# schemat.net
KiCad netlist of a schematic drawn in EAGLE
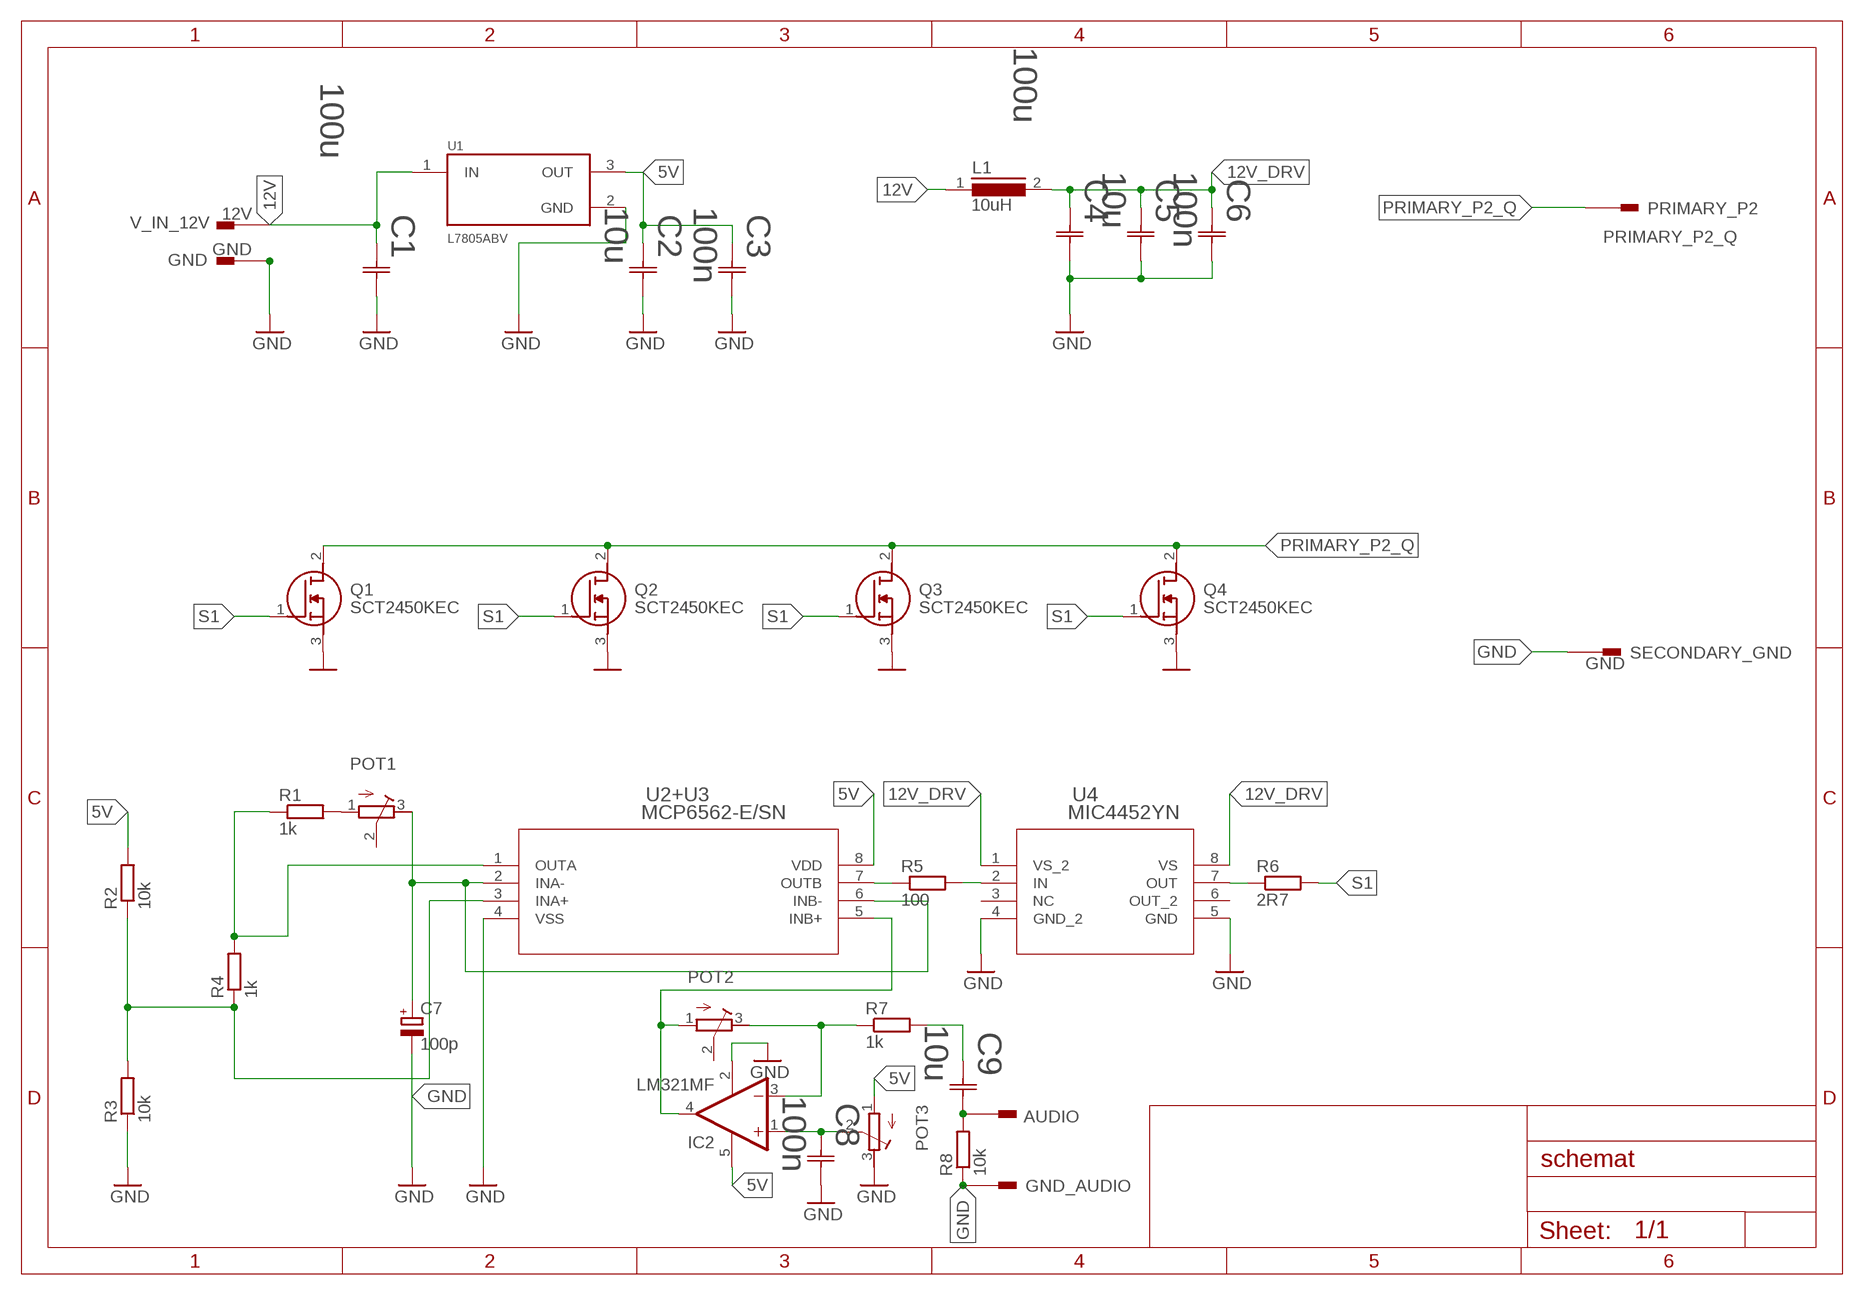
[diagram p0: schematic, sheet 1]

(export (version "E")
  (design (tool "Eeschema 10.0.6"))
  (components
    (comp (ref "AUDIO")
      (value "PIN1-2")
      (footprint "eagle-import:62221")
      (fields (field (name "MF") "TYCO ELECTRONICS") (field (name "MPN") "62221-1"))
      (libsource (lib "eagle-import") (part "PIN1-2"))
    )
    (comp (ref "C1")
      (value "100u")
      (footprint "eagle-import:CAP_YX_6P3X11_RUB")
      (fields
        (field (name "MANUFACTURER_PART_NUMBER") "35ZLH100MEFC6.3X11")
        (field (name "COPYRIGHT") "Copyright (C) 2024 Ultra Librarian. All rights reserved.")
      )
      (libsource (lib "eagle-import") (part "35ZLH100MEFC6.3X11"))
    )
    (comp (ref "C2")
      (value "10u")
      (footprint "eagle-import:CAP_5_X_5_PAN")
      (fields
        (field (name "MANUFACTURER_PART_NUMBER") "ECEA1EKS100")
        (field (name "COPYRIGHT") "Copyright (C) 2024 Ultra Librarian. All rights reserved.")
      )
      (libsource (lib "eagle-import") (part "ECEA1EKS100"))
    )
    (comp (ref "C3")
      (value "100n")
      (footprint "eagle-import:CAP_0402_WAL")
      (fields
        (field (name "MANUFACTURER_PART_NUMBER") "0402B104K250CT")
        (field (name "COPYRIGHT") "Copyright (C) 2024 Ultra Librarian. All rights reserved.")
      )
      (libsource (lib "eagle-import") (part "0402B104K250CT"))
    )
    (comp (ref "C4")
      (value "100u")
      (footprint "eagle-import:CAP_YX_6P3X11_RUB")
      (fields
        (field (name "MANUFACTURER_PART_NUMBER") "35ZLH100MEFC6.3X11")
        (field (name "COPYRIGHT") "Copyright (C) 2024 Ultra Librarian. All rights reserved.")
      )
      (libsource (lib "eagle-import") (part "35ZLH100MEFC6.3X11"))
    )
    (comp (ref "C5")
      (value "10u")
      (footprint "eagle-import:CAP_5_X_5_PAN")
      (fields
        (field (name "MANUFACTURER_PART_NUMBER") "ECEA1EKS100")
        (field (name "COPYRIGHT") "Copyright (C) 2024 Ultra Librarian. All rights reserved.")
      )
      (libsource (lib "eagle-import") (part "ECEA1EKS100"))
    )
    (comp (ref "C6")
      (value "100n")
      (footprint "eagle-import:CAP_0402_WAL")
      (fields
        (field (name "MANUFACTURER_PART_NUMBER") "0402B104K250CT")
        (field (name "COPYRIGHT") "Copyright (C) 2024 Ultra Librarian. All rights reserved.")
      )
      (libsource (lib "eagle-import") (part "0402B104K250CT"))
    )
    (comp (ref "C7")
      (value "100p")
      (footprint "eagle-import:E1,8-4")
      (libsource (lib "eagle-import") (part "CPOL-EUE1.8-4"))
    )
    (comp (ref "C8")
      (value "100n")
      (footprint "eagle-import:CAP_0402_WAL")
      (fields
        (field (name "MANUFACTURER_PART_NUMBER") "0402B104K250CT")
        (field (name "COPYRIGHT") "Copyright (C) 2024 Ultra Librarian. All rights reserved.")
      )
      (libsource (lib "eagle-import") (part "0402B104K250CT"))
    )
    (comp (ref "C9")
      (value "10u")
      (footprint "eagle-import:CAP_5_X_5_PAN")
      (fields
        (field (name "MANUFACTURER_PART_NUMBER") "ECEA1EKS100")
        (field (name "COPYRIGHT") "Copyright (C) 2024 Ultra Librarian. All rights reserved.")
      )
      (libsource (lib "eagle-import") (part "ECEA1EKS100"))
    )
    (comp (ref "GND")
      (value "GND")
      (footprint "eagle-import:62221")
      (fields (field (name "MF") "TYCO ELECTRONICS") (field (name "MPN") "62221-1"))
      (libsource (lib "eagle-import") (part "PIN1-2"))
    )
    (comp (ref "GND_AUDIO")
      (value "GND")
      (footprint "eagle-import:62221")
      (fields (field (name "MF") "TYCO ELECTRONICS") (field (name "MPN") "62221-1"))
      (libsource (lib "eagle-import") (part "PIN1-2"))
    )
    (comp (ref "IC2")
      (value "LM321MF")
      (footprint "eagle-import:SOT23-5")
      (libsource (lib "eagle-import") (part "LM321?MF"))
    )
    (comp (ref "L1")
      (value "10uH")
      (footprint "eagle-import:RKE4")
      (libsource (lib "eagle-import") (part "RKE4"))
    )
    (comp (ref "POT1")
      (value "R-TRIMM64W")
      (footprint "eagle-import:RTRIM64W")
      (libsource (lib "eagle-import") (part "R-TRIMM64W"))
    )
    (comp (ref "POT2")
      (value "R-TRIMM64W")
      (footprint "eagle-import:RTRIM64W")
      (libsource (lib "eagle-import") (part "R-TRIMM64W"))
    )
    (comp (ref "POT3")
      (value "R-TRIMM64W")
      (footprint "eagle-import:RTRIM64W")
      (libsource (lib "eagle-import") (part "R-TRIMM64W"))
    )
    (comp (ref "PRIMARY_P2")
      (value "PRIMARY_P2_Q")
      (footprint "eagle-import:62221")
      (fields (field (name "MF") "TYCO ELECTRONICS") (field (name "MPN") "62221-1"))
      (libsource (lib "eagle-import") (part "PIN1-2"))
    )
    (comp (ref "Q1")
      (value "SCT2450KEC")
      (footprint "eagle-import:TO545P521X1594X2583-3P")
      (libsource (lib "eagle-import") (part "SCT2450KEC"))
    )
    (comp (ref "Q2")
      (value "SCT2450KEC")
      (footprint "eagle-import:TO545P521X1594X2583-3P")
      (libsource (lib "eagle-import") (part "SCT2450KEC"))
    )
    (comp (ref "Q3")
      (value "SCT2450KEC")
      (footprint "eagle-import:TO545P521X1594X2583-3P")
      (libsource (lib "eagle-import") (part "SCT2450KEC"))
    )
    (comp (ref "Q4")
      (value "SCT2450KEC")
      (footprint "eagle-import:TO545P521X1594X2583-3P")
      (libsource (lib "eagle-import") (part "SCT2450KEC"))
    )
    (comp (ref "R1")
      (value "1k")
      (footprint "eagle-import:0204_7")
      (libsource (lib "eagle-import") (part "R-EU_0204/7"))
    )
    (comp (ref "R2")
      (value "10k")
      (footprint "eagle-import:0204_7")
      (libsource (lib "eagle-import") (part "R-EU_0204/7"))
    )
    (comp (ref "R3")
      (value "10k")
      (footprint "eagle-import:0204_7")
      (libsource (lib "eagle-import") (part "R-EU_0204/7"))
    )
    (comp (ref "R4")
      (value "1k")
      (footprint "eagle-import:0204_7")
      (libsource (lib "eagle-import") (part "R-EU_0204/7"))
    )
    (comp (ref "R5")
      (value "100")
      (footprint "eagle-import:0204_7")
      (libsource (lib "eagle-import") (part "R-EU_0204/7"))
    )
    (comp (ref "R6")
      (value "2R7")
      (footprint "eagle-import:0204_7")
      (libsource (lib "eagle-import") (part "R-EU_0204/7"))
    )
    (comp (ref "R7")
      (value "1k")
      (footprint "eagle-import:0204_7")
      (libsource (lib "eagle-import") (part "R-EU_0204/7"))
    )
    (comp (ref "R8")
      (value "10k")
      (footprint "eagle-import:0204_7")
      (libsource (lib "eagle-import") (part "R-EU_0204/7"))
    )
    (comp (ref "SECONDARY_GND")
      (value "GND")
      (footprint "eagle-import:62221")
      (fields (field (name "MF") "TYCO ELECTRONICS") (field (name "MPN") "62221-1"))
      (libsource (lib "eagle-import") (part "PIN1-2"))
    )
    (comp (ref "U1")
      (value "L7805ABV")
      (footprint "eagle-import:TO254P460X1020X1945-3P")
      (fields (field (name "MF") "STMicroelectronics"))
      (libsource (lib "eagle-import") (part "L7805ABV"))
    )
    (comp (ref "U2+U3")
      (value "MCP6562-E/SN")
      (footprint "eagle-import:SOIC8-N_MC_MCH")
      (fields
        (field (name "MANUFACTURER_PART_NUMBER") "mcp6562-e/sn")
        (field (name "COPYRIGHT") "Copyright (C) 2024 Ultra Librarian. All rights reserved.")
      )
      (libsource (lib "eagle-import") (part "MCP6562-E/SN"))
    )
    (comp (ref "U4")
      (value "MIC4452YN")
      (footprint "eagle-import:PDIP8(N)_MCH")
      (fields (field (name "COPYRIGHT") "Copyright (C) 2024 Ultra Librarian. All rights reserved."))
      (libsource (lib "eagle-import") (part "MIC4452YN"))
    )
    (comp (ref "V_IN_12V")
      (value "12V")
      (footprint "eagle-import:62221")
      (fields (field (name "MF") "TYCO ELECTRONICS") (field (name "MPN") "62221-1"))
      (libsource (lib "eagle-import") (part "PIN1-2"))
    )
  )
  (nets
    (net (code "1") (name "5V") (class "Default")
      (node (ref "C2") (pin "1") (pinfunction "1_1") (pintype "passive"))
      (node (ref "C3") (pin "1") (pinfunction "1_1") (pintype "passive"))
      (node (ref "IC2") (pin "5") (pinfunction "V+_5") (pintype "power_in"))
      (node (ref "POT3") (pin "1") (pinfunction "A_1") (pintype "passive"))
      (node (ref "R2") (pin "2") (pinfunction "2_2") (pintype "passive"))
      (node (ref "U1") (pin "3") (pinfunction "OUT_3") (pintype "output"))
      (node (ref "U2+U3") (pin "8") (pinfunction "VDD_8") (pintype "power_in"))
    )
    (net (code "2") (name "12V") (class "Default")
      (node (ref "C1") (pin "1") (pinfunction "1_1") (pintype "passive"))
      (node (ref "L1") (pin "1") (pinfunction "1_1") (pintype "passive"))
      (node (ref "U1") (pin "1") (pinfunction "IN_1") (pintype "input"))
      (node (ref "V_IN_12V") (pin "1") (pinfunction "1_1") (pintype "passive"))
    )
    (net (code "3") (name "12V_DRV") (class "Default")
      (node (ref "C4") (pin "1") (pinfunction "1_1") (pintype "passive"))
      (node (ref "C5") (pin "1") (pinfunction "1_1") (pintype "passive"))
      (node (ref "C6") (pin "1") (pinfunction "1_1") (pintype "passive"))
      (node (ref "L1") (pin "2") (pinfunction "2_2") (pintype "passive"))
      (node (ref "U4") (pin "1") (pinfunction "VS_2_1") (pintype "power_in"))
      (node (ref "U4") (pin "8") (pinfunction "VS_8") (pintype "power_in"))
    )
    (net (code "4") (name "GND") (class "Default")
      (node (ref "C1") (pin "2") (pinfunction "2_2") (pintype "passive"))
      (node (ref "C2") (pin "2") (pinfunction "2_2") (pintype "passive"))
      (node (ref "C3") (pin "2") (pinfunction "2_2") (pintype "passive"))
      (node (ref "C4") (pin "2") (pinfunction "2_2") (pintype "passive"))
      (node (ref "C5") (pin "2") (pinfunction "2_2") (pintype "passive"))
      (node (ref "C6") (pin "2") (pinfunction "2_2") (pintype "passive"))
      (node (ref "C7") (pin "-") (pinfunction "-_-") (pintype "passive"))
      (node (ref "C8") (pin "2") (pinfunction "2_2") (pintype "passive"))
      (node (ref "GND") (pin "1") (pinfunction "1_1") (pintype "passive"))
      (node (ref "GND_AUDIO") (pin "1") (pinfunction "1_1") (pintype "passive"))
      (node (ref "IC2") (pin "2") (pinfunction "V-_2") (pintype "power_in"))
      (node (ref "POT3") (pin "3") (pinfunction "E_3") (pintype "passive"))
      (node (ref "Q1") (pin "3") (pinfunction "S_3") (pintype "output"))
      (node (ref "Q2") (pin "3") (pinfunction "S_3") (pintype "output"))
      (node (ref "Q3") (pin "3") (pinfunction "S_3") (pintype "output"))
      (node (ref "Q4") (pin "3") (pinfunction "S_3") (pintype "output"))
      (node (ref "R3") (pin "1") (pinfunction "1_1") (pintype "passive"))
      (node (ref "R8") (pin "1") (pinfunction "1_1") (pintype "passive"))
      (node (ref "SECONDARY_GND") (pin "1") (pinfunction "1_1") (pintype "passive"))
      (node (ref "U1") (pin "2") (pinfunction "GND_2") (pintype "power_in"))
      (node (ref "U2+U3") (pin "4") (pinfunction "VSS_4") (pintype "power_in"))
      (node (ref "U4") (pin "4") (pinfunction "GND_2_4") (pintype "passive"))
      (node (ref "U4") (pin "5") (pinfunction "GND_5") (pintype "passive"))
    )
    (net (code "5") (name "Net-(AUDIO-Pad1)") (class "Default")
      (node (ref "AUDIO") (pin "1") (pinfunction "1_1") (pintype "passive"))
      (node (ref "C9") (pin "2") (pinfunction "2_2") (pintype "passive"))
      (node (ref "R8") (pin "2") (pinfunction "2_2") (pintype "passive"))
    )
    (net (code "6") (name "Net-(C9-Pad1)") (class "Default")
      (node (ref "C9") (pin "1") (pinfunction "1_1") (pintype "passive"))
      (node (ref "R7") (pin "2") (pinfunction "2_2") (pintype "passive"))
    )
    (net (code "7") (name "Net-(IC2-+IN)") (class "Default")
      (node (ref "C8") (pin "1") (pinfunction "1_1") (pintype "passive"))
      (node (ref "IC2") (pin "1") (pinfunction "+IN_1") (pintype "input"))
      (node (ref "POT3") (pin "2") (pinfunction "S_2") (pintype "passive"))
    )
    (net (code "8") (name "Net-(IC2--IN)") (class "Default")
      (node (ref "IC2") (pin "3") (pinfunction "-IN_3") (pintype "input"))
      (node (ref "POT2") (pin "3") (pinfunction "E_3") (pintype "passive"))
      (node (ref "R7") (pin "1") (pinfunction "1_1") (pintype "passive"))
    )
    (net (code "9") (name "Net-(IC2-OUT)") (class "Default")
      (node (ref "IC2") (pin "4") (pinfunction "OUT_4") (pintype "output"))
      (node (ref "POT2") (pin "1") (pinfunction "A_1") (pintype "passive"))
      (node (ref "U2+U3") (pin "5") (pinfunction "INB+_5") (pintype "input"))
    )
    (net (code "10") (name "Net-(POT1-A)") (class "Default")
      (node (ref "POT1") (pin "1") (pinfunction "A_1") (pintype "passive"))
      (node (ref "R1") (pin "2") (pinfunction "2_2") (pintype "passive"))
    )
    (net (code "11") (name "Net-(POT1-E)") (class "Default")
      (node (ref "C7") (pin "+") (pinfunction "+_+") (pintype "passive"))
      (node (ref "POT1") (pin "3") (pinfunction "E_3") (pintype "passive"))
      (node (ref "U2+U3") (pin "2") (pinfunction "INA-_2") (pintype "input"))
      (node (ref "U2+U3") (pin "6") (pinfunction "INB-_6") (pintype "input"))
    )
    (net (code "12") (name "Net-(U2+U3-INA+)") (class "Default")
      (node (ref "R2") (pin "1") (pinfunction "1_1") (pintype "passive"))
      (node (ref "R3") (pin "2") (pinfunction "2_2") (pintype "passive"))
      (node (ref "R4") (pin "1") (pinfunction "1_1") (pintype "passive"))
      (node (ref "U2+U3") (pin "3") (pinfunction "INA+_3") (pintype "input"))
    )
    (net (code "13") (name "Net-(U2+U3-OUTA)") (class "Default")
      (node (ref "R1") (pin "1") (pinfunction "1_1") (pintype "passive"))
      (node (ref "R4") (pin "2") (pinfunction "2_2") (pintype "passive"))
      (node (ref "U2+U3") (pin "1") (pinfunction "OUTA_1") (pintype "output"))
    )
    (net (code "14") (name "Net-(U2+U3-OUTB)") (class "Default")
      (node (ref "R5") (pin "1") (pinfunction "1_1") (pintype "passive"))
      (node (ref "U2+U3") (pin "7") (pinfunction "OUTB_7") (pintype "output"))
    )
    (net (code "15") (name "Net-(U4-IN)") (class "Default")
      (node (ref "R5") (pin "2") (pinfunction "2_2") (pintype "passive"))
      (node (ref "U4") (pin "2") (pinfunction "IN_2") (pintype "input"))
    )
    (net (code "16") (name "Net-(U4-OUT)") (class "Default")
      (node (ref "R6") (pin "1") (pinfunction "1_1") (pintype "passive"))
      (node (ref "U4") (pin "7") (pinfunction "OUT_7") (pintype "output"))
    )
    (net (code "17") (name "PRIMARY_P2_Q") (class "Default")
      (node (ref "PRIMARY_P2") (pin "1") (pinfunction "1_1") (pintype "passive"))
      (node (ref "Q1") (pin "2") (pinfunction "D_2") (pintype "input"))
      (node (ref "Q2") (pin "2") (pinfunction "D_2") (pintype "input"))
      (node (ref "Q3") (pin "2") (pinfunction "D_2") (pintype "input"))
      (node (ref "Q4") (pin "2") (pinfunction "D_2") (pintype "input"))
    )
    (net (code "18") (name "S1") (class "Default")
      (node (ref "Q1") (pin "1") (pinfunction "G_1") (pintype "input"))
      (node (ref "Q2") (pin "1") (pinfunction "G_1") (pintype "input"))
      (node (ref "Q3") (pin "1") (pinfunction "G_1") (pintype "input"))
      (node (ref "Q4") (pin "1") (pinfunction "G_1") (pintype "input"))
      (node (ref "R6") (pin "2") (pinfunction "2_2") (pintype "passive"))
    )
    (net (code "19") (name "unconnected-(POT1-S-Pad2)") (class "Default")
      (node (ref "POT1") (pin "2") (pinfunction "S_2") (pintype "passive"))
    )
    (net (code "20") (name "unconnected-(POT2-S-Pad2)") (class "Default")
      (node (ref "POT2") (pin "2") (pinfunction "S_2") (pintype "passive"))
    )
    (net (code "21") (name "unconnected-(U4-NC-Pad3)") (class "Default")
      (node (ref "U4") (pin "3") (pinfunction "NC_3") (pintype "no_connect"))
    )
    (net (code "22") (name "unconnected-(U4-OUT_2-Pad6)") (class "Default")
      (node (ref "U4") (pin "6") (pinfunction "OUT_2_6") (pintype "output"))
    )
  )
)
